# LM1117-Fixed-v2_5.net
KiCad netlist of a schematic drawn in EAGLE
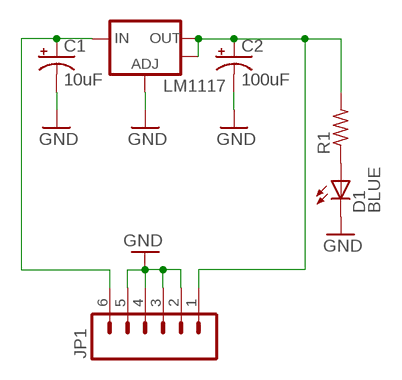
[diagram p0: schematic, sheet 1]

(export (version "E")
  (design (tool "Eeschema 10.0.6"))
  (components
    (comp (ref "C1")
      (value "10uF")
      (footprint "eagle-import:CT7343")
      (libsource (lib "eagle-import") (part "CPOL-USCT7343"))
    )
    (comp (ref "C2")
      (value "100uF")
      (footprint "eagle-import:CT7343")
      (libsource (lib "eagle-import") (part "CPOL-USCT7343"))
    )
    (comp (ref "D1")
      (value "BLUE")
      (footprint "eagle-import:CHIP-LED0805")
      (libsource (lib "eagle-import") (part "LEDCHIP-LED0805"))
    )
    (comp (ref "JP1")
      (value "M06NO_SILK_FEMALE_PTH")
      (footprint "eagle-import:1X06_NO_SILK")
      (libsource (lib "eagle-import") (part "M06NO_SILK_FEMALE_PTH"))
    )
    (comp (ref "LM1117")
      (value "V_REG_LM1117SOT223")
      (footprint "eagle-import:SOT223")
      (libsource (lib "eagle-import") (part "V_REG_LM1117SOT223"))
    )
    (comp (ref "R1")
      (value "R-US_R0805")
      (footprint "eagle-import:R0805")
      (libsource (lib "eagle-import") (part "R-US_R0805"))
    )
  )
  (nets
    (net (code "1") (name "GND") (class "Default")
      (node (ref "C1") (pin "-") (pinfunction "-_-") (pintype "passive"))
      (node (ref "C2") (pin "-") (pinfunction "-_-") (pintype "passive"))
      (node (ref "D1") (pin "C") (pinfunction "C_C") (pintype "passive"))
      (node (ref "JP1") (pin "2") (pinfunction "2_2") (pintype "passive"))
      (node (ref "JP1") (pin "3") (pinfunction "3_3") (pintype "passive"))
      (node (ref "JP1") (pin "4") (pinfunction "4_4") (pintype "passive"))
      (node (ref "JP1") (pin "5") (pinfunction "5_5") (pintype "passive"))
      (node (ref "LM1117") (pin "1") (pinfunction "ADJ_1") (pintype "input"))
    )
    (net (code "2") (name "Net-(C2-Pad+)") (class "Default")
      (node (ref "C2") (pin "+") (pinfunction "+_+") (pintype "passive"))
      (node (ref "JP1") (pin "1") (pinfunction "1_1") (pintype "passive"))
      (node (ref "LM1117") (pin "2") (pinfunction "OUT_2") (pintype "output"))
      (node (ref "LM1117") (pin "4") (pinfunction "OUT_4") (pintype "output"))
      (node (ref "R1") (pin "2") (pinfunction "2_2") (pintype "passive"))
    )
    (net (code "3") (name "Net-(D1-PadA)") (class "Default")
      (node (ref "D1") (pin "A") (pinfunction "A_A") (pintype "passive"))
      (node (ref "R1") (pin "1") (pinfunction "1_1") (pintype "passive"))
    )
    (net (code "4") (name "Net-(LM1117-IN)") (class "Default")
      (node (ref "C1") (pin "+") (pinfunction "+_+") (pintype "passive"))
      (node (ref "JP1") (pin "6") (pinfunction "6_6") (pintype "passive"))
      (node (ref "LM1117") (pin "3") (pinfunction "IN_3") (pintype "input"))
    )
  )
)
